# template.net
KiCad netlist of a schematic drawn in EAGLE
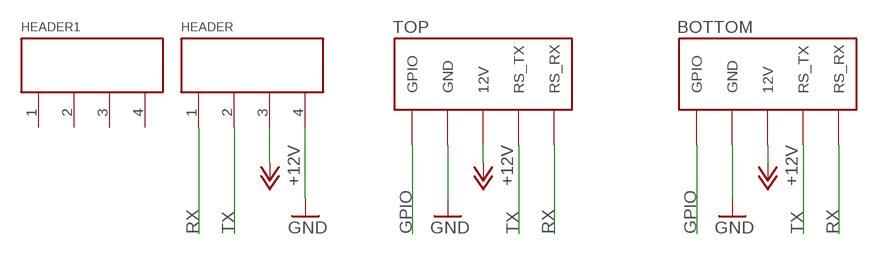
[diagram p0: schematic, sheet 1]

(export (version "E")
  (design (tool "Eeschema 10.0.6"))
  (components
    (comp (ref "BOTTOM")
      (value "STEROWNIK-PINY_5PIN_BOTTOM")
      (footprint "eagle-import:STEROWNIK-PINY_5PIN_BOTTOM")
      (libsource (lib "eagle-import") (part "STEROWNIK-PINY_5PIN_BOTTOM"))
    )
    (comp (ref "HEADER")
      (value "TBMP5104RO-KF")
      (footprint "eagle-import:TBMP5104RO-KF")
      (libsource (lib "eagle-import") (part "TBMP5104RO-KF"))
    )
    (comp (ref "HEADER1")
      (value "TBMP5104RO-KF")
      (footprint "eagle-import:TBMP5104RO-KF")
      (libsource (lib "eagle-import") (part "TBMP5104RO-KF"))
    )
    (comp (ref "TOP")
      (value "STEROWNIK-PINY_5PIN")
      (footprint "eagle-import:STEROWNIK-PINY_5PIN")
      (libsource (lib "eagle-import") (part "STEROWNIK-PINY_5PIN"))
    )
  )
  (nets
    (net (code "1") (name "+12V") (class "Default")
      (node (ref "BOTTOM") (pin "12") (pinfunction "12V_12") (pintype "bidirectional"))
      (node (ref "HEADER") (pin "3") (pinfunction "3_3") (pintype "bidirectional"))
      (node (ref "TOP") (pin "12V") (pinfunction "12V_12V") (pintype "bidirectional"))
    )
    (net (code "2") (name "/GPIO") (class "Default")
      (node (ref "BOTTOM") (pin "GPIO1") (pinfunction "GPIO_GPIO1") (pintype "bidirectional"))
      (node (ref "TOP") (pin "GPIO1") (pinfunction "GPIO_GPIO1") (pintype "bidirectional"))
    )
    (net (code "3") (name "/RX") (class "Default")
      (node (ref "BOTTOM") (pin "RS_RX") (pinfunction "RS_RX_RS_RX") (pintype "bidirectional"))
      (node (ref "HEADER") (pin "1") (pinfunction "1_1") (pintype "bidirectional"))
      (node (ref "TOP") (pin "RS_RX") (pinfunction "RS_RX_RS_RX") (pintype "bidirectional"))
    )
    (net (code "4") (name "/TX") (class "Default")
      (node (ref "BOTTOM") (pin "RS_TX") (pinfunction "RS_TX_RS_TX") (pintype "bidirectional"))
      (node (ref "HEADER") (pin "2") (pinfunction "2_2") (pintype "bidirectional"))
      (node (ref "TOP") (pin "RS_TX") (pinfunction "RS_TX_RS_TX") (pintype "bidirectional"))
    )
    (net (code "5") (name "GND") (class "Default")
      (node (ref "BOTTOM") (pin "GND") (pinfunction "GND_GND") (pintype "bidirectional"))
      (node (ref "HEADER") (pin "4") (pinfunction "4_4") (pintype "bidirectional"))
      (node (ref "TOP") (pin "GND") (pinfunction "GND_GND") (pintype "bidirectional"))
    )
    (net (code "6") (name "unconnected-(HEADER1-Pad1)") (class "Default")
      (node (ref "HEADER1") (pin "1") (pinfunction "1_1") (pintype "bidirectional"))
    )
    (net (code "7") (name "unconnected-(HEADER1-Pad2)") (class "Default")
      (node (ref "HEADER1") (pin "2") (pinfunction "2_2") (pintype "bidirectional"))
    )
    (net (code "8") (name "unconnected-(HEADER1-Pad3)") (class "Default")
      (node (ref "HEADER1") (pin "3") (pinfunction "3_3") (pintype "bidirectional"))
    )
    (net (code "9") (name "unconnected-(HEADER1-Pad4)") (class "Default")
      (node (ref "HEADER1") (pin "4") (pinfunction "4_4") (pintype "bidirectional"))
    )
  )
)
